# recco-rig.net
KiCad netlist of a schematic drawn in EAGLE
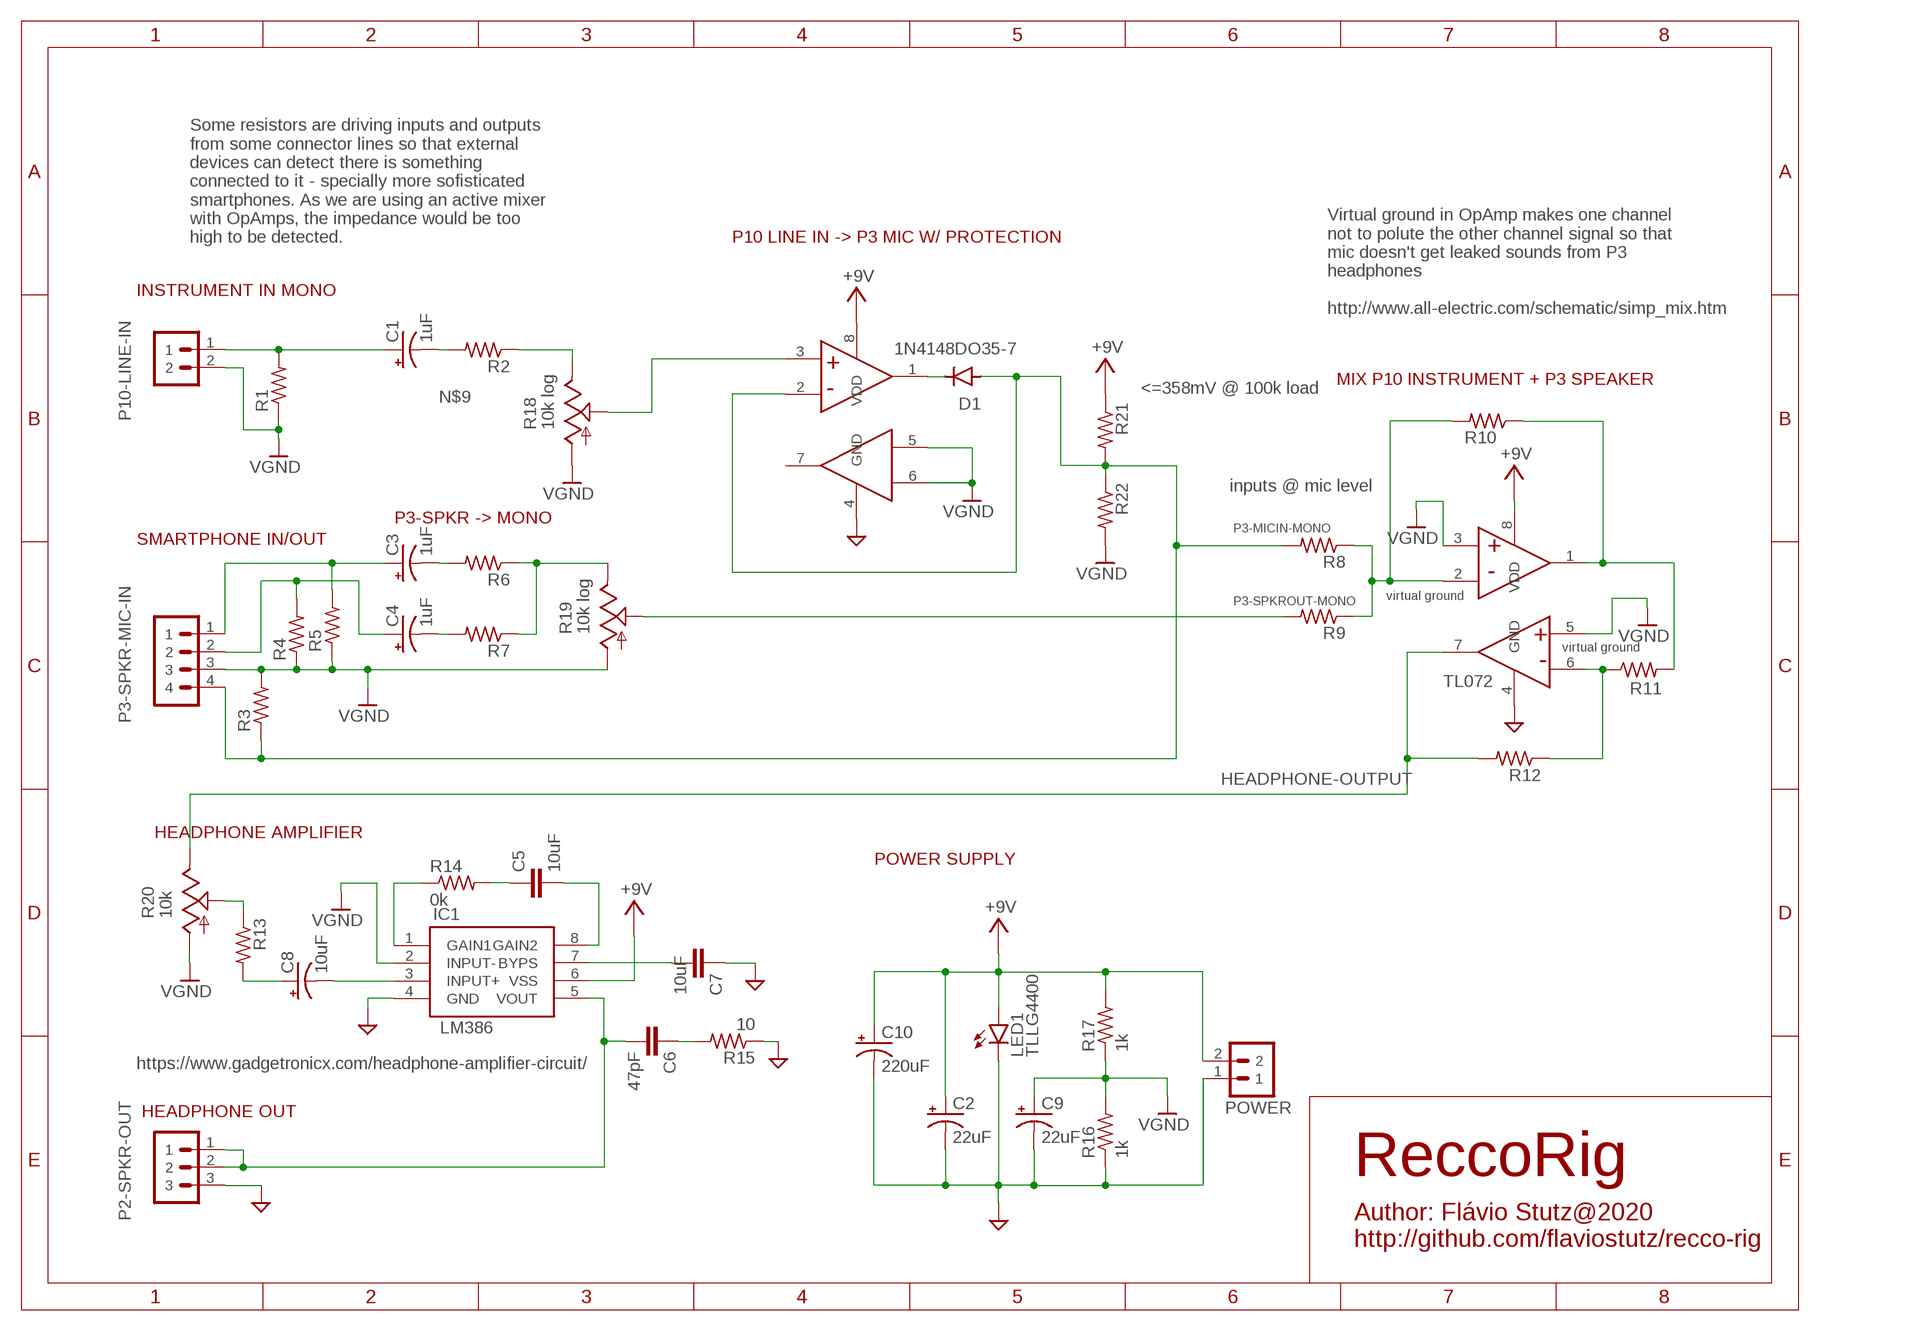
[diagram p0: schematic, sheet 1]

(export (version "E")
  (design (tool "Eeschema 10.0.6"))
  (components
    (comp (ref "C1")
      (value "1uF")
      (footprint "eagle-import:E2,5-6E")
      (libsource (lib "eagle-import") (part "CPOL-USE2,5-6E"))
    )
    (comp (ref "C2")
      (value "22uF")
      (footprint "eagle-import:E2,5-6E")
      (libsource (lib "eagle-import") (part "CPOL-USE2,5-6E"))
    )
    (comp (ref "C3")
      (value "1uF")
      (footprint "eagle-import:E2,5-6E")
      (libsource (lib "eagle-import") (part "CPOL-USE2,5-6E"))
    )
    (comp (ref "C4")
      (value "1uF")
      (footprint "eagle-import:E2,5-6E")
      (libsource (lib "eagle-import") (part "CPOL-USE2,5-6E"))
    )
    (comp (ref "C5")
      (value "10uF")
      (footprint "eagle-import:C050-024X044")
      (libsource (lib "eagle-import") (part "C-EU050-024X044"))
    )
    (comp (ref "C6")
      (value "47pF")
      (footprint "eagle-import:C050-024X044")
      (libsource (lib "eagle-import") (part "C-EU050-024X044"))
    )
    (comp (ref "C7")
      (value "10uF")
      (footprint "eagle-import:C050-024X044")
      (libsource (lib "eagle-import") (part "C-EU050-024X044"))
    )
    (comp (ref "C8")
      (value "10uF")
      (footprint "eagle-import:E2,5-6E")
      (libsource (lib "eagle-import") (part "CPOL-USE2,5-6E"))
    )
    (comp (ref "C9")
      (value "22uF")
      (footprint "eagle-import:E2,5-6E")
      (libsource (lib "eagle-import") (part "CPOL-USE2,5-6E"))
    )
    (comp (ref "C10")
      (value "220uF")
      (footprint "eagle-import:E2,5-6E")
      (libsource (lib "eagle-import") (part "CPOL-USE2,5-6E"))
    )
    (comp (ref "D1")
      (value "1N4148DO35-7")
      (footprint "eagle-import:DO35-7")
      (libsource (lib "eagle-import") (part "1N4148DO35-7"))
    )
    (comp (ref "IC1")
      (value "LM386")
      (footprint "eagle-import:PDIP-8PIN")
      (libsource (lib "eagle-import") (part "LM386"))
    )
    (comp (ref "IC2")
      (value "TL072-OPAMP")
      (footprint "eagle-import:PDIP-8PIN")
      (fields (field (name "SPICEPREFIX") "X"))
      (libsource (lib "eagle-import") (part "TL072-OPAMP"))
    )
    (comp (ref "LED1")
      (value "TLLG4400")
      (footprint "eagle-import:LED3MM")
      (fields (field (name "MF") "VISHAY SEMICONDUCTOR"))
      (libsource (lib "eagle-import") (part "TLLG4400"))
    )
    (comp (ref "P2-SPKR-OUT")
      (value "PIN-HEADER-3PIN")
      (footprint "eagle-import:PIN-HEADER-3PIN")
      (libsource (lib "eagle-import") (part "PIN-HEADER-3PIN"))
    )
    (comp (ref "P3-SPKR-MIC-IN")
      (value "PIN-HEADER-4PIN")
      (footprint "eagle-import:PIN-HEADER-4PIN")
      (libsource (lib "eagle-import") (part "PIN-HEADER-4PIN"))
    )
    (comp (ref "P10-LINE-IN")
      (value "PIN-HEADER-2PIN")
      (footprint "eagle-import:PIN-HEADER-2PIN")
      (libsource (lib "eagle-import") (part "PIN-HEADER-2PIN"))
    )
    (comp (ref "POWER")
      (value "PIN-HEADER-2PIN")
      (footprint "eagle-import:PIN-HEADER-2PIN")
      (libsource (lib "eagle-import") (part "PIN-HEADER-2PIN"))
    )
    (comp (ref "R1")
      (value "10k")
      (footprint "eagle-import:RESISTOR-V1")
      (libsource (lib "eagle-import") (part "RESISTORV1"))
    )
    (comp (ref "R2")
      (value "300")
      (footprint "eagle-import:RESISTOR-V1")
      (libsource (lib "eagle-import") (part "RESISTORV1"))
    )
    (comp (ref "R3")
      (value "1k")
      (footprint "eagle-import:RESISTOR-V1")
      (libsource (lib "eagle-import") (part "RESISTORV1"))
    )
    (comp (ref "R4")
      (value "1k")
      (footprint "eagle-import:RESISTOR-V1")
      (fields (field (name "SPICEPREFIX") "R"))
      (libsource (lib "eagle-import") (part "RESISTORV1"))
    )
    (comp (ref "R5")
      (value "1k")
      (footprint "eagle-import:RESISTOR-V1")
      (libsource (lib "eagle-import") (part "RESISTORV1"))
    )
    (comp (ref "R6")
      (value "300")
      (footprint "eagle-import:RESISTOR-V1")
      (libsource (lib "eagle-import") (part "RESISTORV1"))
    )
    (comp (ref "R7")
      (value "300")
      (footprint "eagle-import:RESISTOR-V1")
      (libsource (lib "eagle-import") (part "RESISTORV1"))
    )
    (comp (ref "R8")
      (value "10k")
      (footprint "eagle-import:RESISTOR-V1")
      (libsource (lib "eagle-import") (part "RESISTORV1"))
    )
    (comp (ref "R9")
      (value "10k")
      (footprint "eagle-import:RESISTOR-V1")
      (libsource (lib "eagle-import") (part "RESISTORV1"))
    )
    (comp (ref "R10")
      (value "10k")
      (footprint "eagle-import:RESISTOR-V1")
      (libsource (lib "eagle-import") (part "RESISTORV1"))
    )
    (comp (ref "R11")
      (value "10k")
      (footprint "eagle-import:RESISTOR-V1")
      (libsource (lib "eagle-import") (part "RESISTORV1"))
    )
    (comp (ref "R12")
      (value "10k")
      (footprint "eagle-import:RESISTOR-V1")
      (libsource (lib "eagle-import") (part "RESISTORV1"))
    )
    (comp (ref "R13")
      (value "100")
      (footprint "eagle-import:RESISTOR-V1")
      (libsource (lib "eagle-import") (part "RESISTORV1"))
    )
    (comp (ref "R14")
      (value "0k")
      (footprint "eagle-import:0309V")
      (libsource (lib "eagle-import") (part "R-US_0309/V"))
    )
    (comp (ref "R15")
      (value "10")
      (footprint "eagle-import:0309V")
      (libsource (lib "eagle-import") (part "R-US_0309/V"))
    )
    (comp (ref "R16")
      (value "1k")
      (footprint "eagle-import:0309V")
      (libsource (lib "eagle-import") (part "R-US_0309/V"))
    )
    (comp (ref "R17")
      (value "1k")
      (footprint "eagle-import:0309V")
      (libsource (lib "eagle-import") (part "R-US_0309/V"))
    )
    (comp (ref "R18")
      (value "10k log")
      (footprint "eagle-import:B25U")
      (libsource (lib "eagle-import") (part "TRIM_US-B25U"))
    )
    (comp (ref "R19")
      (value "10k log")
      (footprint "eagle-import:B25U")
      (libsource (lib "eagle-import") (part "TRIM_US-B25U"))
    )
    (comp (ref "R20")
      (value "10k")
      (footprint "eagle-import:B25U")
      (libsource (lib "eagle-import") (part "TRIM_US-B25U"))
    )
    (comp (ref "R21")
      (value "10k")
      (footprint "eagle-import:RESISTOR-V1")
      (libsource (lib "eagle-import") (part "RESISTORV1"))
    )
    (comp (ref "R22")
      (value "1k")
      (footprint "eagle-import:RESISTOR-V1")
      (libsource (lib "eagle-import") (part "RESISTORV1"))
    )
    (comp (ref "U$12")
      (value "TL072-OPAMP")
      (footprint "eagle-import:PDIP-8PIN")
      (libsource (lib "eagle-import") (part "TL072-OPAMP"))
    )
  )
  (nets
    (net (code "1") (name "+9V") (class "Default")
      (node (ref "C10") (pin "+") (pinfunction "+_+") (pintype "passive"))
      (node (ref "C2") (pin "+") (pinfunction "+_+") (pintype "passive"))
      (node (ref "IC1") (pin "6") (pinfunction "VSS_6") (pintype "power_in"))
      (node (ref "IC2") (pin "8") (pinfunction "VDD_8") (pintype "power_in"))
      (node (ref "LED1") (pin "A") (pinfunction "A_A") (pintype "passive"))
      (node (ref "POWER") (pin "2") (pinfunction "2_2") (pintype "passive"))
      (node (ref "R17") (pin "2") (pinfunction "2_2") (pintype "passive"))
      (node (ref "R21") (pin "1") (pinfunction "1_1") (pintype "passive"))
      (node (ref "U$12") (pin "8") (pinfunction "VDD_8") (pintype "power_in"))
    )
    (net (code "2") (name "/HEADPHONE-OUTPUT") (class "Default")
      (node (ref "IC2") (pin "7") (pinfunction "2OUT_7") (pintype "output"))
      (node (ref "R12") (pin "2") (pinfunction "2_2") (pintype "passive"))
      (node (ref "R20") (pin "E") (pinfunction "E_E") (pintype "passive"))
    )
    (net (code "3") (name "/N$9") (class "Default")
      (node (ref "R18") (pin "E") (pinfunction "E_E") (pintype "passive"))
      (node (ref "R2") (pin "1") (pinfunction "1_1") (pintype "passive"))
    )
    (net (code "4") (name "/P3-MICIN-MONO") (class "Default")
      (node (ref "D1") (pin "A") (pinfunction "A_A") (pintype "passive"))
      (node (ref "P3-SPKR-MIC-IN") (pin "4") (pinfunction "4_4") (pintype "passive"))
      (node (ref "R21") (pin "2") (pinfunction "2_2") (pintype "passive"))
      (node (ref "R22") (pin "1") (pinfunction "1_1") (pintype "passive"))
      (node (ref "R3") (pin "1") (pinfunction "1_1") (pintype "passive"))
      (node (ref "R8") (pin "2") (pinfunction "2_2") (pintype "passive"))
      (node (ref "U$12") (pin "2") (pinfunction "1IN-_2") (pintype "input"))
    )
    (net (code "5") (name "/P3-SPKROUT-MONO") (class "Default")
      (node (ref "R19") (pin "S") (pinfunction "S_S") (pintype "passive"))
      (node (ref "R9") (pin "2") (pinfunction "2_2") (pintype "passive"))
    )
    (net (code "6") (name "GND") (class "Default")
      (node (ref "C10") (pin "-") (pinfunction "-_-") (pintype "passive"))
      (node (ref "C2") (pin "-") (pinfunction "-_-") (pintype "passive"))
      (node (ref "C7") (pin "1") (pinfunction "1_1") (pintype "passive"))
      (node (ref "C9") (pin "-") (pinfunction "-_-") (pintype "passive"))
      (node (ref "IC1") (pin "4") (pinfunction "GND_4") (pintype "power_in"))
      (node (ref "IC2") (pin "4") (pinfunction "GND_4") (pintype "power_in"))
      (node (ref "LED1") (pin "K") (pinfunction "C_K") (pintype "passive"))
      (node (ref "P2-SPKR-OUT") (pin "3") (pinfunction "3_3") (pintype "passive"))
      (node (ref "POWER") (pin "1") (pinfunction "1_1") (pintype "passive"))
      (node (ref "R15") (pin "1") (pinfunction "1_1") (pintype "passive"))
      (node (ref "R16") (pin "1") (pinfunction "1_1") (pintype "passive"))
      (node (ref "U$12") (pin "4") (pinfunction "GND_4") (pintype "power_in"))
    )
    (net (code "7") (name "Net-(C1-Pad+)") (class "Default")
      (node (ref "C1") (pin "+") (pinfunction "+_+") (pintype "passive"))
      (node (ref "P10-LINE-IN") (pin "1") (pinfunction "1_1") (pintype "passive"))
      (node (ref "R1") (pin "2") (pinfunction "2_2") (pintype "passive"))
    )
    (net (code "8") (name "Net-(C1-Pad-)") (class "Default")
      (node (ref "C1") (pin "-") (pinfunction "-_-") (pintype "passive"))
      (node (ref "R2") (pin "2") (pinfunction "2_2") (pintype "passive"))
    )
    (net (code "9") (name "Net-(C3-Pad+)") (class "Default")
      (node (ref "C3") (pin "+") (pinfunction "+_+") (pintype "passive"))
      (node (ref "P3-SPKR-MIC-IN") (pin "1") (pinfunction "1_1") (pintype "passive"))
      (node (ref "R5") (pin "2") (pinfunction "2_2") (pintype "passive"))
    )
    (net (code "10") (name "Net-(C3-Pad-)") (class "Default")
      (node (ref "C3") (pin "-") (pinfunction "-_-") (pintype "passive"))
      (node (ref "R6") (pin "2") (pinfunction "2_2") (pintype "passive"))
    )
    (net (code "11") (name "Net-(C4-Pad+)") (class "Default")
      (node (ref "C4") (pin "+") (pinfunction "+_+") (pintype "passive"))
      (node (ref "P3-SPKR-MIC-IN") (pin "2") (pinfunction "2_2") (pintype "passive"))
      (node (ref "R4") (pin "2") (pinfunction "2_2") (pintype "passive"))
    )
    (net (code "12") (name "Net-(C4-Pad-)") (class "Default")
      (node (ref "C4") (pin "-") (pinfunction "-_-") (pintype "passive"))
      (node (ref "R7") (pin "2") (pinfunction "2_2") (pintype "passive"))
    )
    (net (code "13") (name "Net-(C5-Pad1)") (class "Default")
      (node (ref "C5") (pin "1") (pinfunction "1_1") (pintype "passive"))
      (node (ref "R14") (pin "2") (pinfunction "2_2") (pintype "passive"))
    )
    (net (code "14") (name "Net-(C6-Pad1)") (class "Default")
      (node (ref "C6") (pin "1") (pinfunction "1_1") (pintype "passive"))
      (node (ref "R15") (pin "2") (pinfunction "2_2") (pintype "passive"))
    )
    (net (code "15") (name "Net-(C8-Pad+)") (class "Default")
      (node (ref "C8") (pin "+") (pinfunction "+_+") (pintype "passive"))
      (node (ref "R13") (pin "2") (pinfunction "2_2") (pintype "passive"))
    )
    (net (code "16") (name "Net-(IC1-BYPS)") (class "Default")
      (node (ref "C7") (pin "2") (pinfunction "2_2") (pintype "passive"))
      (node (ref "IC1") (pin "7") (pinfunction "BYPS_7") (pintype "output"))
    )
    (net (code "17") (name "Net-(IC1-GAIN1)") (class "Default")
      (node (ref "IC1") (pin "1") (pinfunction "GAIN1_1") (pintype "passive"))
      (node (ref "R14") (pin "1") (pinfunction "1_1") (pintype "passive"))
    )
    (net (code "18") (name "Net-(IC1-GAIN2)") (class "Default")
      (node (ref "C5") (pin "2") (pinfunction "2_2") (pintype "passive"))
      (node (ref "IC1") (pin "8") (pinfunction "GAIN2_8") (pintype "passive"))
    )
    (net (code "19") (name "Net-(IC1-INPUT+)") (class "Default")
      (node (ref "C8") (pin "-") (pinfunction "-_-") (pintype "passive"))
      (node (ref "IC1") (pin "3") (pinfunction "INPUT+_3") (pintype "input"))
    )
    (net (code "20") (name "Net-(IC1-VOUT)") (class "Default")
      (node (ref "C6") (pin "2") (pinfunction "2_2") (pintype "passive"))
      (node (ref "IC1") (pin "5") (pinfunction "VOUT_5") (pintype "output"))
      (node (ref "P2-SPKR-OUT") (pin "1") (pinfunction "1_1") (pintype "passive"))
      (node (ref "P2-SPKR-OUT") (pin "2") (pinfunction "2_2") (pintype "passive"))
    )
    (net (code "21") (name "Net-(IC2-1IN-)") (class "Default")
      (node (ref "IC2") (pin "2") (pinfunction "1IN-_2") (pintype "input"))
      (node (ref "R10") (pin "2") (pinfunction "2_2") (pintype "passive"))
      (node (ref "R8") (pin "1") (pinfunction "1_1") (pintype "passive"))
      (node (ref "R9") (pin "1") (pinfunction "1_1") (pintype "passive"))
    )
    (net (code "22") (name "Net-(IC2-1OUT)") (class "Default")
      (node (ref "IC2") (pin "1") (pinfunction "1OUT_1") (pintype "output"))
      (node (ref "R10") (pin "1") (pinfunction "1_1") (pintype "passive"))
      (node (ref "R11") (pin "2") (pinfunction "2_2") (pintype "passive"))
    )
    (net (code "23") (name "Net-(IC2-2IN-)") (class "Default")
      (node (ref "IC2") (pin "6") (pinfunction "2IN-_6") (pintype "input"))
      (node (ref "R11") (pin "1") (pinfunction "1_1") (pintype "passive"))
      (node (ref "R12") (pin "1") (pinfunction "1_1") (pintype "passive"))
    )
    (net (code "24") (name "Net-(R13-Pad1)") (class "Default")
      (node (ref "R13") (pin "1") (pinfunction "1_1") (pintype "passive"))
      (node (ref "R20") (pin "S") (pinfunction "S_S") (pintype "passive"))
    )
    (net (code "25") (name "Net-(R19-PadE)") (class "Default")
      (node (ref "R19") (pin "E") (pinfunction "E_E") (pintype "passive"))
      (node (ref "R6") (pin "1") (pinfunction "1_1") (pintype "passive"))
      (node (ref "R7") (pin "1") (pinfunction "1_1") (pintype "passive"))
    )
    (net (code "26") (name "Net-(U$12-1IN+)") (class "Default")
      (node (ref "R18") (pin "S") (pinfunction "S_S") (pintype "passive"))
      (node (ref "U$12") (pin "3") (pinfunction "1IN+_3") (pintype "input"))
    )
    (net (code "27") (name "Net-(U$12-1OUT)") (class "Default")
      (node (ref "D1") (pin "C") (pinfunction "C_C") (pintype "passive"))
      (node (ref "U$12") (pin "1") (pinfunction "1OUT_1") (pintype "output"))
    )
    (net (code "28") (name "VGND") (class "Default")
      (node (ref "C9") (pin "+") (pinfunction "+_+") (pintype "passive"))
      (node (ref "IC1") (pin "2") (pinfunction "INPUT-_2") (pintype "input"))
      (node (ref "IC2") (pin "3") (pinfunction "1IN+_3") (pintype "input"))
      (node (ref "IC2") (pin "5") (pinfunction "2IN+_5") (pintype "input"))
      (node (ref "P10-LINE-IN") (pin "2") (pinfunction "2_2") (pintype "passive"))
      (node (ref "P3-SPKR-MIC-IN") (pin "3") (pinfunction "3_3") (pintype "passive"))
      (node (ref "R1") (pin "1") (pinfunction "1_1") (pintype "passive"))
      (node (ref "R16") (pin "2") (pinfunction "2_2") (pintype "passive"))
      (node (ref "R17") (pin "1") (pinfunction "1_1") (pintype "passive"))
      (node (ref "R18") (pin "A") (pinfunction "A_A") (pintype "passive"))
      (node (ref "R19") (pin "A") (pinfunction "A_A") (pintype "passive"))
      (node (ref "R20") (pin "A") (pinfunction "A_A") (pintype "passive"))
      (node (ref "R22") (pin "2") (pinfunction "2_2") (pintype "passive"))
      (node (ref "R3") (pin "2") (pinfunction "2_2") (pintype "passive"))
      (node (ref "R4") (pin "1") (pinfunction "1_1") (pintype "passive"))
      (node (ref "R5") (pin "1") (pinfunction "1_1") (pintype "passive"))
      (node (ref "U$12") (pin "5") (pinfunction "2IN+_5") (pintype "input"))
      (node (ref "U$12") (pin "6") (pinfunction "2IN-_6") (pintype "input"))
    )
    (net (code "29") (name "unconnected-(U$12-2OUT-Pad7)") (class "Default")
      (node (ref "U$12") (pin "7") (pinfunction "2OUT_7") (pintype "output"))
    )
  )
)
